# INT_RACK.net
KiCad netlist of a schematic drawn in EAGLE
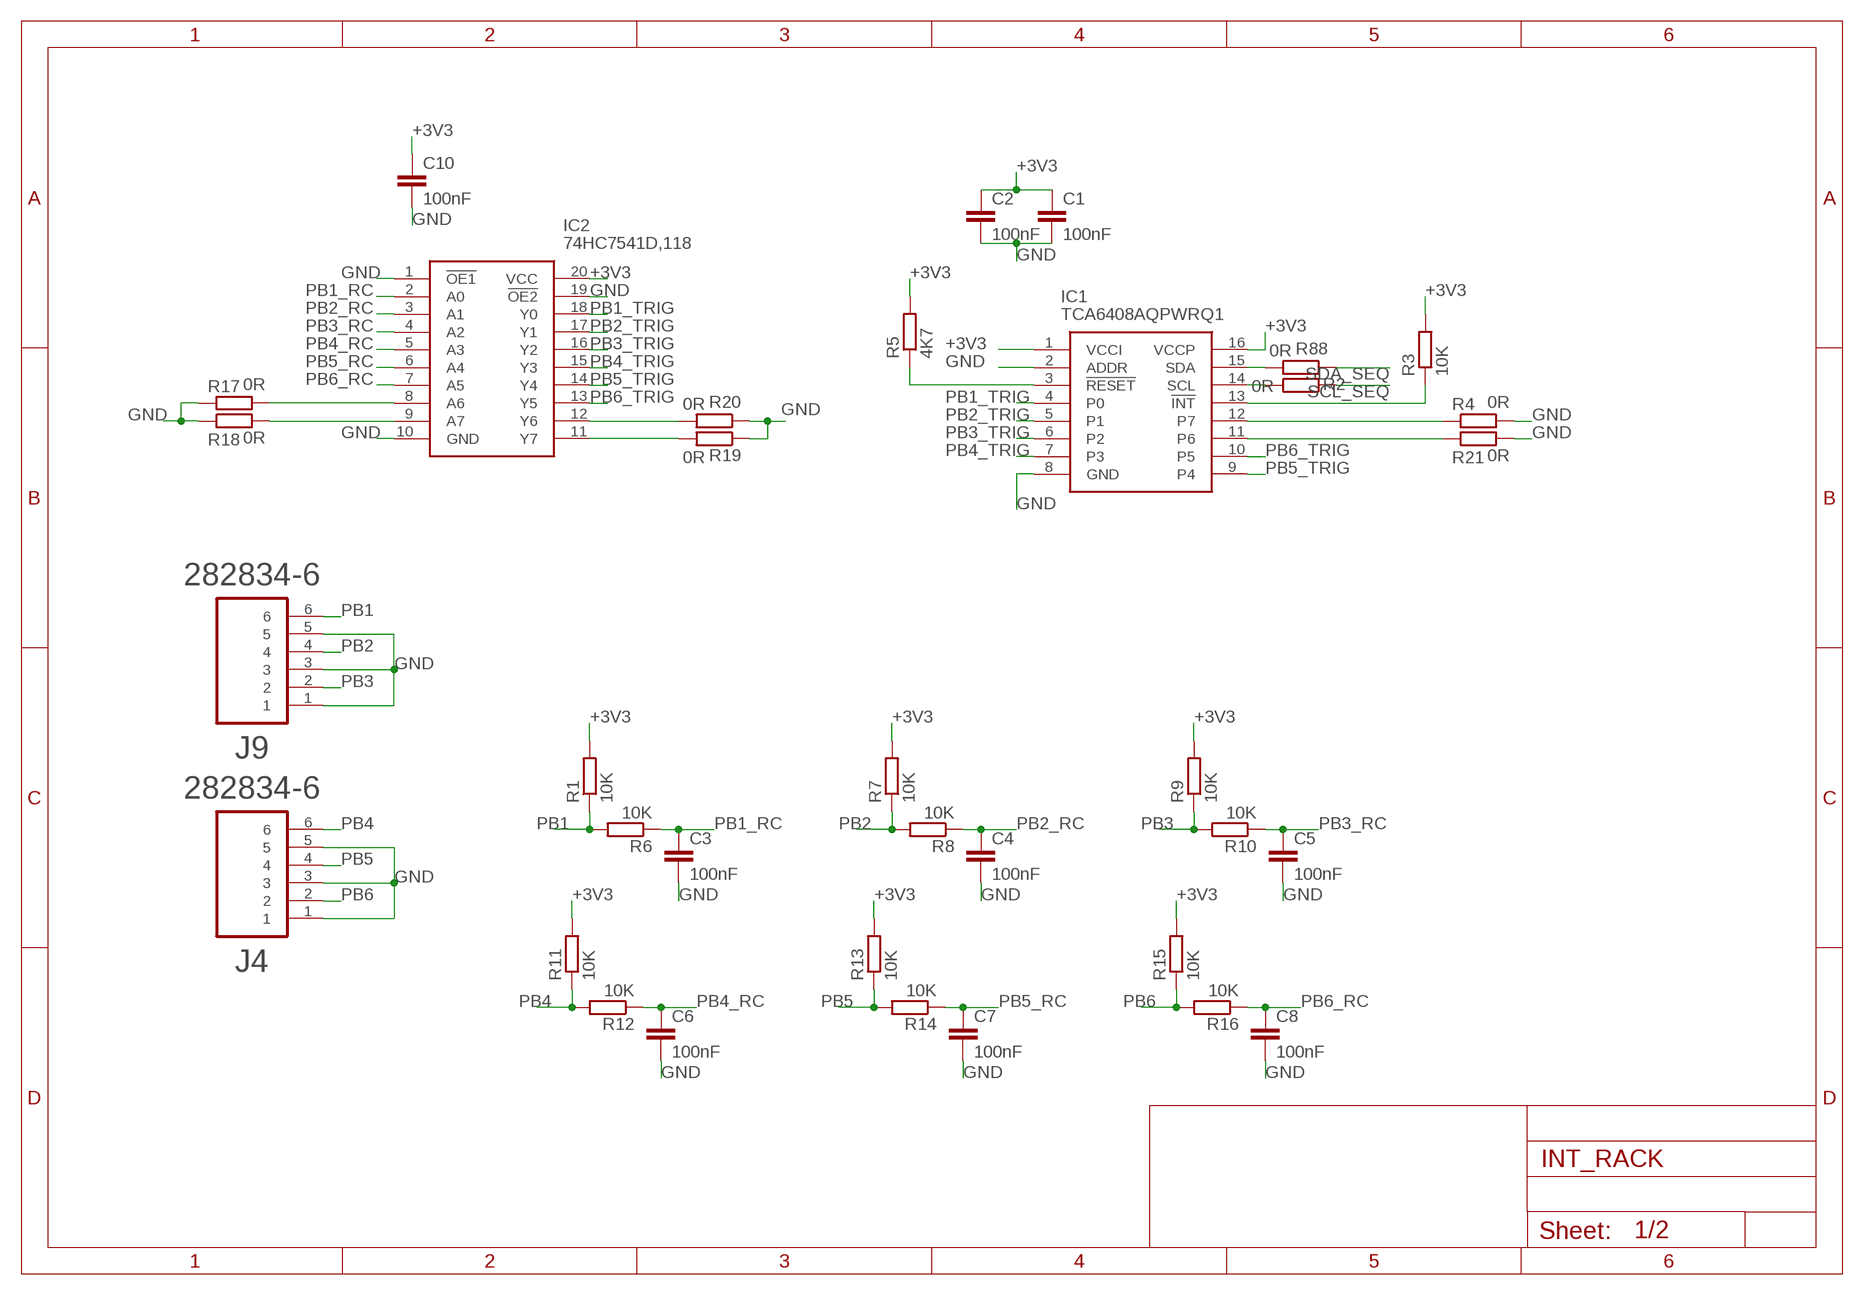
[diagram p0: schematic, sheet 1]
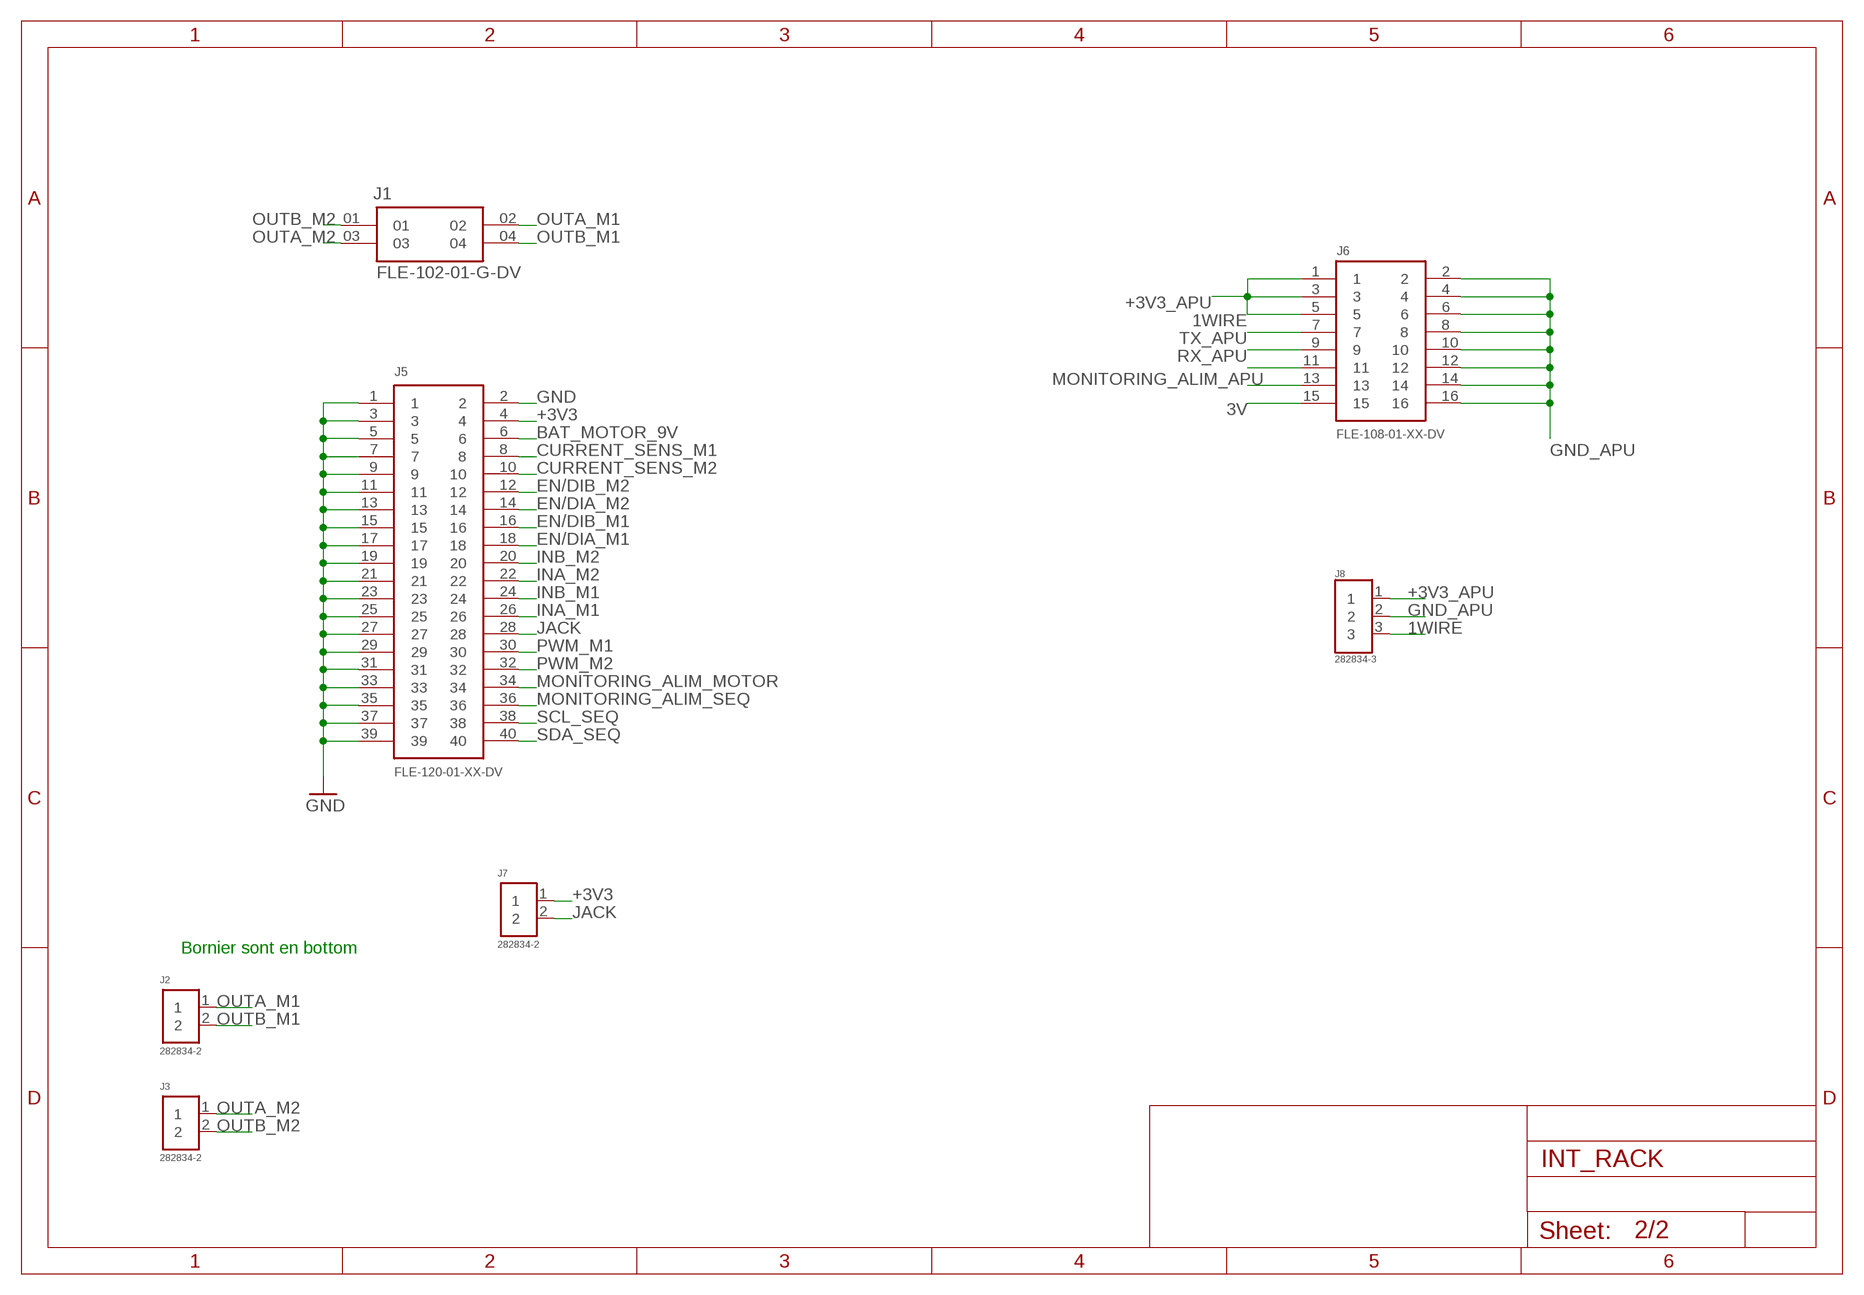
[diagram p1: schematic, sheet 2]

(export (version "E")
  (design (tool "Eeschema 10.0.6"))
  (components
    (comp (ref "C1")
      (value "100nF")
      (footprint "eagle-import:C0805")
      (libsource (lib "eagle-import") (part "C-EUC0805"))
    )
    (comp (ref "C2")
      (value "100nF")
      (footprint "eagle-import:C0805")
      (libsource (lib "eagle-import") (part "C-EUC0805"))
    )
    (comp (ref "C3")
      (value "100nF")
      (footprint "eagle-import:C0805")
      (libsource (lib "eagle-import") (part "C-EUC0805"))
    )
    (comp (ref "C4")
      (value "100nF")
      (footprint "eagle-import:C0805")
      (libsource (lib "eagle-import") (part "C-EUC0805"))
    )
    (comp (ref "C5")
      (value "100nF")
      (footprint "eagle-import:C0805")
      (libsource (lib "eagle-import") (part "C-EUC0805"))
    )
    (comp (ref "C6")
      (value "100nF")
      (footprint "eagle-import:C0805")
      (libsource (lib "eagle-import") (part "C-EUC0805"))
    )
    (comp (ref "C7")
      (value "100nF")
      (footprint "eagle-import:C0805")
      (libsource (lib "eagle-import") (part "C-EUC0805"))
    )
    (comp (ref "C8")
      (value "100nF")
      (footprint "eagle-import:C0805")
      (libsource (lib "eagle-import") (part "C-EUC0805"))
    )
    (comp (ref "C10")
      (value "100nF")
      (footprint "eagle-import:C0805")
      (libsource (lib "eagle-import") (part "C-EUC0805"))
    )
    (comp (ref "IC1")
      (value "TCA6408AQPWRQ1")
      (footprint "eagle-import:SOP65P640X120-16N")
      (fields (field (name "MOUSER_PART_NUMBER") "595-TCA6408AQPWRQ1"))
      (libsource (lib "eagle-import") (part "TCA6408AQPWRQ1"))
    )
    (comp (ref "IC2")
      (value "74HC7541D,118")
      (footprint "eagle-import:SOIC127P1032X265-20N")
      (fields (field (name "MOUSER_PART_NUMBER") "771-74HC7541D-T"))
      (libsource (lib "eagle-import") (part "74HC7541D,118"))
    )
    (comp (ref "J4")
      (value "282834-6")
      (footprint "eagle-import:TE_282834-6")
      (fields (field (name "MF") "TE Connectivity"))
      (libsource (lib "eagle-import") (part "282834-6"))
    )
    (comp (ref "J9")
      (value "282834-6")
      (footprint "eagle-import:TE_282834-6")
      (fields (field (name "MF") "TE Connectivity"))
      (libsource (lib "eagle-import") (part "282834-6"))
    )
    (comp (ref "R1")
      (value "10K")
      (footprint "eagle-import:R0603")
      (libsource (lib "eagle-import") (part "R-EU_R0603"))
    )
    (comp (ref "R2")
      (value "0R")
      (footprint "eagle-import:R0603")
      (libsource (lib "eagle-import") (part "R-EU_R0603"))
    )
    (comp (ref "R3")
      (value "10K")
      (footprint "eagle-import:R0603")
      (libsource (lib "eagle-import") (part "R-EU_R0603"))
    )
    (comp (ref "R4")
      (value "0R")
      (footprint "eagle-import:R0603")
      (libsource (lib "eagle-import") (part "R-EU_R0603"))
    )
    (comp (ref "R5")
      (value "4K7")
      (footprint "eagle-import:R0603")
      (libsource (lib "eagle-import") (part "R-EU_R0603"))
    )
    (comp (ref "R6")
      (value "10K")
      (footprint "eagle-import:R0603")
      (libsource (lib "eagle-import") (part "R-EU_R0603"))
    )
    (comp (ref "R7")
      (value "10K")
      (footprint "eagle-import:R0603")
      (libsource (lib "eagle-import") (part "R-EU_R0603"))
    )
    (comp (ref "R8")
      (value "10K")
      (footprint "eagle-import:R0603")
      (libsource (lib "eagle-import") (part "R-EU_R0603"))
    )
    (comp (ref "R9")
      (value "10K")
      (footprint "eagle-import:R0603")
      (libsource (lib "eagle-import") (part "R-EU_R0603"))
    )
    (comp (ref "R10")
      (value "10K")
      (footprint "eagle-import:R0603")
      (libsource (lib "eagle-import") (part "R-EU_R0603"))
    )
    (comp (ref "R11")
      (value "10K")
      (footprint "eagle-import:R0603")
      (libsource (lib "eagle-import") (part "R-EU_R0603"))
    )
    (comp (ref "R12")
      (value "10K")
      (footprint "eagle-import:R0603")
      (libsource (lib "eagle-import") (part "R-EU_R0603"))
    )
    (comp (ref "R13")
      (value "10K")
      (footprint "eagle-import:R0603")
      (libsource (lib "eagle-import") (part "R-EU_R0603"))
    )
    (comp (ref "R14")
      (value "10K")
      (footprint "eagle-import:R0603")
      (libsource (lib "eagle-import") (part "R-EU_R0603"))
    )
    (comp (ref "R15")
      (value "10K")
      (footprint "eagle-import:R0603")
      (libsource (lib "eagle-import") (part "R-EU_R0603"))
    )
    (comp (ref "R16")
      (value "10K")
      (footprint "eagle-import:R0603")
      (libsource (lib "eagle-import") (part "R-EU_R0603"))
    )
    (comp (ref "R17")
      (value "0R")
      (footprint "eagle-import:R0603")
      (libsource (lib "eagle-import") (part "R-EU_R0603"))
    )
    (comp (ref "R18")
      (value "0R")
      (footprint "eagle-import:R0603")
      (libsource (lib "eagle-import") (part "R-EU_R0603"))
    )
    (comp (ref "R19")
      (value "0R")
      (footprint "eagle-import:R0603")
      (libsource (lib "eagle-import") (part "R-EU_R0603"))
    )
    (comp (ref "R20")
      (value "0R")
      (footprint "eagle-import:R0603")
      (libsource (lib "eagle-import") (part "R-EU_R0603"))
    )
    (comp (ref "R21")
      (value "0R")
      (footprint "eagle-import:R0603")
      (libsource (lib "eagle-import") (part "R-EU_R0603"))
    )
    (comp (ref "R88")
      (value "0R")
      (footprint "eagle-import:R0603")
      (libsource (lib "eagle-import") (part "R-EU_R0603"))
    )
    (comp (ref "J1")
      (value "FLE-102-01-G-DV")
      (footprint "eagle-import:SAMTEC_FLE-102-01-G-DV")
      (fields (field (name "MF") "Samtec"))
      (libsource (lib "eagle-import") (part "FLE-102-01-G-DV"))
    )
    (comp (ref "J2")
      (value "282834-2")
      (footprint "eagle-import:CONN_282834-2")
      (fields (field (name "MF") "TE Connectivity"))
      (libsource (lib "eagle-import") (part "282834-2"))
    )
    (comp (ref "J3")
      (value "282834-2")
      (footprint "eagle-import:CONN_282834-2")
      (fields (field (name "MF") "TE Connectivity"))
      (libsource (lib "eagle-import") (part "282834-2"))
    )
    (comp (ref "J5")
      (value "FLE-120-01-XX-DV")
      (footprint "eagle-import:FLE-120-01-XX-DV")
      (fields (field (name "MF") "Samtec") (field (name "MP") "FLE-120-01-G-DV"))
      (libsource (lib "eagle-import") (part "FLE-120-01-XX-DV"))
    )
    (comp (ref "J6")
      (value "FLE-108-01-XX-DV")
      (footprint "eagle-import:FLE-108-01-XX-DV")
      (fields (field (name "MF") "Samtec") (field (name "MP") "FLE-108-01-G-DV"))
      (libsource (lib "eagle-import") (part "FLE-108-01-XX-DV"))
    )
    (comp (ref "J7")
      (value "282834-2")
      (footprint "eagle-import:CONN_282834-2")
      (fields (field (name "MF") "TE Connectivity"))
      (libsource (lib "eagle-import") (part "282834-2"))
    )
    (comp (ref "J8")
      (value "282834-3")
      (footprint "eagle-import:TE_282834-3")
      (fields (field (name "MF") "TE Connectivity"))
      (libsource (lib "eagle-import") (part "282834-3"))
    )
  )
  (nets
    (net (code "1") (name "+3V3") (class "Default")
      (node (ref "C1") (pin "1") (pinfunction "1_1") (pintype "passive"))
      (node (ref "C10") (pin "1") (pinfunction "1_1") (pintype "passive"))
      (node (ref "C2") (pin "1") (pinfunction "1_1") (pintype "passive"))
      (node (ref "IC1") (pin "1") (pinfunction "VCCI_1") (pintype "bidirectional"))
      (node (ref "IC1") (pin "16") (pinfunction "VCCP_16") (pintype "bidirectional"))
      (node (ref "IC2") (pin "20") (pinfunction "VCC_20") (pintype "bidirectional"))
      (node (ref "J5") (pin "4") (pinfunction "4_4") (pintype "bidirectional"))
      (node (ref "J7") (pin "1") (pinfunction "1_1") (pintype "passive"))
      (node (ref "R1") (pin "2") (pinfunction "2_2") (pintype "passive"))
      (node (ref "R11") (pin "2") (pinfunction "2_2") (pintype "passive"))
      (node (ref "R13") (pin "2") (pinfunction "2_2") (pintype "passive"))
      (node (ref "R15") (pin "2") (pinfunction "2_2") (pintype "passive"))
      (node (ref "R3") (pin "2") (pinfunction "2_2") (pintype "passive"))
      (node (ref "R5") (pin "2") (pinfunction "2_2") (pintype "passive"))
      (node (ref "R7") (pin "2") (pinfunction "2_2") (pintype "passive"))
      (node (ref "R9") (pin "2") (pinfunction "2_2") (pintype "passive"))
    )
    (net (code "2") (name "+3V3_APU") (class "Default")
      (node (ref "J6") (pin "1") (pinfunction "1_1") (pintype "bidirectional"))
      (node (ref "J6") (pin "3") (pinfunction "3_3") (pintype "bidirectional"))
      (node (ref "J6") (pin "5") (pinfunction "5_5") (pintype "bidirectional"))
      (node (ref "J8") (pin "1") (pinfunction "1_1") (pintype "passive"))
    )
    (net (code "3") (name "1WIRE") (class "Default")
      (node (ref "J6") (pin "7") (pinfunction "7_7") (pintype "bidirectional"))
      (node (ref "J8") (pin "3") (pinfunction "3_3") (pintype "passive"))
    )
    (net (code "4") (name "3V") (class "Default")
      (node (ref "J6") (pin "15") (pinfunction "15_15") (pintype "bidirectional"))
    )
    (net (code "5") (name "BAT_MOTOR_9V") (class "Default")
      (node (ref "J5") (pin "6") (pinfunction "6_6") (pintype "bidirectional"))
    )
    (net (code "6") (name "CURRENT_SENS_M1") (class "Default")
      (node (ref "J5") (pin "8") (pinfunction "8_8") (pintype "bidirectional"))
    )
    (net (code "7") (name "CURRENT_SENS_M2") (class "Default")
      (node (ref "J5") (pin "10") (pinfunction "10_10") (pintype "bidirectional"))
    )
    (net (code "8") (name "EN{slash}DIA_M1") (class "Default")
      (node (ref "J5") (pin "18") (pinfunction "18_18") (pintype "bidirectional"))
    )
    (net (code "9") (name "EN{slash}DIA_M2") (class "Default")
      (node (ref "J5") (pin "14") (pinfunction "14_14") (pintype "bidirectional"))
    )
    (net (code "10") (name "EN{slash}DIB_M1") (class "Default")
      (node (ref "J5") (pin "16") (pinfunction "16_16") (pintype "bidirectional"))
    )
    (net (code "11") (name "EN{slash}DIB_M2") (class "Default")
      (node (ref "J5") (pin "12") (pinfunction "12_12") (pintype "bidirectional"))
    )
    (net (code "12") (name "GND") (class "Default")
      (node (ref "C1") (pin "2") (pinfunction "2_2") (pintype "passive"))
      (node (ref "C10") (pin "2") (pinfunction "2_2") (pintype "passive"))
      (node (ref "C2") (pin "2") (pinfunction "2_2") (pintype "passive"))
      (node (ref "C3") (pin "2") (pinfunction "2_2") (pintype "passive"))
      (node (ref "C4") (pin "2") (pinfunction "2_2") (pintype "passive"))
      (node (ref "C5") (pin "2") (pinfunction "2_2") (pintype "passive"))
      (node (ref "C6") (pin "2") (pinfunction "2_2") (pintype "passive"))
      (node (ref "C7") (pin "2") (pinfunction "2_2") (pintype "passive"))
      (node (ref "C8") (pin "2") (pinfunction "2_2") (pintype "passive"))
      (node (ref "IC1") (pin "2") (pinfunction "ADDR_2") (pintype "bidirectional"))
      (node (ref "IC1") (pin "8") (pinfunction "GND_8") (pintype "bidirectional"))
      (node (ref "IC2") (pin "1") (pinfunction "~{OE1}_1") (pintype "bidirectional"))
      (node (ref "IC2") (pin "10") (pinfunction "GND_10") (pintype "bidirectional"))
      (node (ref "IC2") (pin "19") (pinfunction "~{OE2}_19") (pintype "bidirectional"))
      (node (ref "J4") (pin "1") (pinfunction "1_1") (pintype "passive"))
      (node (ref "J4") (pin "3") (pinfunction "3_3") (pintype "passive"))
      (node (ref "J4") (pin "5") (pinfunction "5_5") (pintype "passive"))
      (node (ref "J5") (pin "1") (pinfunction "1_1") (pintype "bidirectional"))
      (node (ref "J5") (pin "11") (pinfunction "11_11") (pintype "bidirectional"))
      (node (ref "J5") (pin "13") (pinfunction "13_13") (pintype "bidirectional"))
      (node (ref "J5") (pin "15") (pinfunction "15_15") (pintype "bidirectional"))
      (node (ref "J5") (pin "17") (pinfunction "17_17") (pintype "bidirectional"))
      (node (ref "J5") (pin "19") (pinfunction "19_19") (pintype "bidirectional"))
      (node (ref "J5") (pin "2") (pinfunction "2_2") (pintype "bidirectional"))
      (node (ref "J5") (pin "21") (pinfunction "21_21") (pintype "bidirectional"))
      (node (ref "J5") (pin "23") (pinfunction "23_23") (pintype "bidirectional"))
      (node (ref "J5") (pin "25") (pinfunction "25_25") (pintype "bidirectional"))
      (node (ref "J5") (pin "27") (pinfunction "27_27") (pintype "bidirectional"))
      (node (ref "J5") (pin "29") (pinfunction "29_29") (pintype "bidirectional"))
      (node (ref "J5") (pin "3") (pinfunction "3_3") (pintype "bidirectional"))
      (node (ref "J5") (pin "31") (pinfunction "31_31") (pintype "bidirectional"))
      (node (ref "J5") (pin "33") (pinfunction "33_33") (pintype "bidirectional"))
      (node (ref "J5") (pin "35") (pinfunction "35_35") (pintype "bidirectional"))
      (node (ref "J5") (pin "37") (pinfunction "37_37") (pintype "bidirectional"))
      (node (ref "J5") (pin "39") (pinfunction "39_39") (pintype "bidirectional"))
      (node (ref "J5") (pin "5") (pinfunction "5_5") (pintype "bidirectional"))
      (node (ref "J5") (pin "7") (pinfunction "7_7") (pintype "bidirectional"))
      (node (ref "J5") (pin "9") (pinfunction "9_9") (pintype "bidirectional"))
      (node (ref "J9") (pin "1") (pinfunction "1_1") (pintype "passive"))
      (node (ref "J9") (pin "3") (pinfunction "3_3") (pintype "passive"))
      (node (ref "J9") (pin "5") (pinfunction "5_5") (pintype "passive"))
      (node (ref "R17") (pin "1") (pinfunction "1_1") (pintype "passive"))
      (node (ref "R18") (pin "1") (pinfunction "1_1") (pintype "passive"))
      (node (ref "R19") (pin "1") (pinfunction "1_1") (pintype "passive"))
      (node (ref "R20") (pin "1") (pinfunction "1_1") (pintype "passive"))
      (node (ref "R21") (pin "2") (pinfunction "2_2") (pintype "passive"))
      (node (ref "R4") (pin "2") (pinfunction "2_2") (pintype "passive"))
    )
    (net (code "13") (name "GND_APU") (class "Default")
      (node (ref "J6") (pin "10") (pinfunction "10_10") (pintype "bidirectional"))
      (node (ref "J6") (pin "12") (pinfunction "12_12") (pintype "bidirectional"))
      (node (ref "J6") (pin "14") (pinfunction "14_14") (pintype "bidirectional"))
      (node (ref "J6") (pin "16") (pinfunction "16_16") (pintype "bidirectional"))
      (node (ref "J6") (pin "2") (pinfunction "2_2") (pintype "bidirectional"))
      (node (ref "J6") (pin "4") (pinfunction "4_4") (pintype "bidirectional"))
      (node (ref "J6") (pin "6") (pinfunction "6_6") (pintype "bidirectional"))
      (node (ref "J6") (pin "8") (pinfunction "8_8") (pintype "bidirectional"))
      (node (ref "J8") (pin "2") (pinfunction "2_2") (pintype "passive"))
    )
    (net (code "14") (name "INA_M1") (class "Default")
      (node (ref "J5") (pin "26") (pinfunction "26_26") (pintype "bidirectional"))
    )
    (net (code "15") (name "INA_M2") (class "Default")
      (node (ref "J5") (pin "22") (pinfunction "22_22") (pintype "bidirectional"))
    )
    (net (code "16") (name "INB_M1") (class "Default")
      (node (ref "J5") (pin "24") (pinfunction "24_24") (pintype "bidirectional"))
    )
    (net (code "17") (name "INB_M2") (class "Default")
      (node (ref "J5") (pin "20") (pinfunction "20_20") (pintype "bidirectional"))
    )
    (net (code "18") (name "JACK") (class "Default")
      (node (ref "J5") (pin "28") (pinfunction "28_28") (pintype "bidirectional"))
      (node (ref "J7") (pin "2") (pinfunction "2_2") (pintype "passive"))
    )
    (net (code "19") (name "MONITORING_ALIM_APU") (class "Default")
      (node (ref "J6") (pin "13") (pinfunction "13_13") (pintype "bidirectional"))
    )
    (net (code "20") (name "MONITORING_ALIM_MOTOR") (class "Default")
      (node (ref "J5") (pin "34") (pinfunction "34_34") (pintype "bidirectional"))
    )
    (net (code "21") (name "MONITORING_ALIM_SEQ") (class "Default")
      (node (ref "J5") (pin "36") (pinfunction "36_36") (pintype "bidirectional"))
    )
    (net (code "22") (name "Net-(IC1-P6)") (class "Default")
      (node (ref "IC1") (pin "11") (pinfunction "P6_11") (pintype "bidirectional"))
      (node (ref "R21") (pin "1") (pinfunction "1_1") (pintype "passive"))
    )
    (net (code "23") (name "Net-(IC1-P7)") (class "Default")
      (node (ref "IC1") (pin "12") (pinfunction "P7_12") (pintype "bidirectional"))
      (node (ref "R4") (pin "1") (pinfunction "1_1") (pintype "passive"))
    )
    (net (code "24") (name "Net-(IC1-SCL)") (class "Default")
      (node (ref "IC1") (pin "14") (pinfunction "SCL_14") (pintype "bidirectional"))
      (node (ref "R2") (pin "2") (pinfunction "2_2") (pintype "passive"))
    )
    (net (code "25") (name "Net-(IC1-SDA)") (class "Default")
      (node (ref "IC1") (pin "15") (pinfunction "SDA_15") (pintype "bidirectional"))
      (node (ref "R88") (pin "2") (pinfunction "2_2") (pintype "passive"))
    )
    (net (code "26") (name "Net-(IC1-~{INT})") (class "Default")
      (node (ref "IC1") (pin "13") (pinfunction "~{INT}_13") (pintype "bidirectional"))
      (node (ref "R3") (pin "1") (pinfunction "1_1") (pintype "passive"))
    )
    (net (code "27") (name "Net-(IC1-~{RESET})") (class "Default")
      (node (ref "IC1") (pin "3") (pinfunction "~{RESET}_3") (pintype "bidirectional"))
      (node (ref "R5") (pin "1") (pinfunction "1_1") (pintype "passive"))
    )
    (net (code "28") (name "Net-(IC2-A6)") (class "Default")
      (node (ref "IC2") (pin "8") (pinfunction "A6_8") (pintype "bidirectional"))
      (node (ref "R17") (pin "2") (pinfunction "2_2") (pintype "passive"))
    )
    (net (code "29") (name "Net-(IC2-A7)") (class "Default")
      (node (ref "IC2") (pin "9") (pinfunction "A7_9") (pintype "bidirectional"))
      (node (ref "R18") (pin "2") (pinfunction "2_2") (pintype "passive"))
    )
    (net (code "30") (name "Net-(IC2-Y6)") (class "Default")
      (node (ref "IC2") (pin "12") (pinfunction "Y6_12") (pintype "bidirectional"))
      (node (ref "R20") (pin "2") (pinfunction "2_2") (pintype "passive"))
    )
    (net (code "31") (name "Net-(IC2-Y7)") (class "Default")
      (node (ref "IC2") (pin "11") (pinfunction "Y7_11") (pintype "bidirectional"))
      (node (ref "R19") (pin "2") (pinfunction "2_2") (pintype "passive"))
    )
    (net (code "32") (name "OUTA_M1") (class "Default")
      (node (ref "J1") (pin "02") (pinfunction "02_02") (pintype "passive"))
      (node (ref "J2") (pin "1") (pinfunction "1_1") (pintype "passive"))
    )
    (net (code "33") (name "OUTA_M2") (class "Default")
      (node (ref "J1") (pin "03") (pinfunction "03_03") (pintype "passive"))
      (node (ref "J3") (pin "1") (pinfunction "1_1") (pintype "passive"))
    )
    (net (code "34") (name "OUTB_M1") (class "Default")
      (node (ref "J1") (pin "04") (pinfunction "04_04") (pintype "passive"))
      (node (ref "J2") (pin "2") (pinfunction "2_2") (pintype "passive"))
    )
    (net (code "35") (name "OUTB_M2") (class "Default")
      (node (ref "J1") (pin "01") (pinfunction "01_01") (pintype "passive"))
      (node (ref "J3") (pin "2") (pinfunction "2_2") (pintype "passive"))
    )
    (net (code "36") (name "PB1") (class "Default")
      (node (ref "J9") (pin "6") (pinfunction "6_6") (pintype "passive"))
      (node (ref "R1") (pin "1") (pinfunction "1_1") (pintype "passive"))
      (node (ref "R6") (pin "2") (pinfunction "2_2") (pintype "passive"))
    )
    (net (code "37") (name "PB1_RC") (class "Default")
      (node (ref "C3") (pin "1") (pinfunction "1_1") (pintype "passive"))
      (node (ref "IC2") (pin "2") (pinfunction "A0_2") (pintype "bidirectional"))
      (node (ref "R6") (pin "1") (pinfunction "1_1") (pintype "passive"))
    )
    (net (code "38") (name "PB1_TRIG") (class "Default")
      (node (ref "IC1") (pin "4") (pinfunction "P0_4") (pintype "bidirectional"))
      (node (ref "IC2") (pin "18") (pinfunction "Y0_18") (pintype "bidirectional"))
    )
    (net (code "39") (name "PB2") (class "Default")
      (node (ref "J9") (pin "4") (pinfunction "4_4") (pintype "passive"))
      (node (ref "R7") (pin "1") (pinfunction "1_1") (pintype "passive"))
      (node (ref "R8") (pin "2") (pinfunction "2_2") (pintype "passive"))
    )
    (net (code "40") (name "PB2_RC") (class "Default")
      (node (ref "C4") (pin "1") (pinfunction "1_1") (pintype "passive"))
      (node (ref "IC2") (pin "3") (pinfunction "A1_3") (pintype "bidirectional"))
      (node (ref "R8") (pin "1") (pinfunction "1_1") (pintype "passive"))
    )
    (net (code "41") (name "PB2_TRIG") (class "Default")
      (node (ref "IC1") (pin "5") (pinfunction "P1_5") (pintype "bidirectional"))
      (node (ref "IC2") (pin "17") (pinfunction "Y1_17") (pintype "bidirectional"))
    )
    (net (code "42") (name "PB3") (class "Default")
      (node (ref "J9") (pin "2") (pinfunction "2_2") (pintype "passive"))
      (node (ref "R10") (pin "2") (pinfunction "2_2") (pintype "passive"))
      (node (ref "R9") (pin "1") (pinfunction "1_1") (pintype "passive"))
    )
    (net (code "43") (name "PB3_RC") (class "Default")
      (node (ref "C5") (pin "1") (pinfunction "1_1") (pintype "passive"))
      (node (ref "IC2") (pin "4") (pinfunction "A2_4") (pintype "bidirectional"))
      (node (ref "R10") (pin "1") (pinfunction "1_1") (pintype "passive"))
    )
    (net (code "44") (name "PB3_TRIG") (class "Default")
      (node (ref "IC1") (pin "6") (pinfunction "P2_6") (pintype "bidirectional"))
      (node (ref "IC2") (pin "16") (pinfunction "Y2_16") (pintype "bidirectional"))
    )
    (net (code "45") (name "PB4") (class "Default")
      (node (ref "J4") (pin "6") (pinfunction "6_6") (pintype "passive"))
      (node (ref "R11") (pin "1") (pinfunction "1_1") (pintype "passive"))
      (node (ref "R12") (pin "2") (pinfunction "2_2") (pintype "passive"))
    )
    (net (code "46") (name "PB4_RC") (class "Default")
      (node (ref "C6") (pin "1") (pinfunction "1_1") (pintype "passive"))
      (node (ref "IC2") (pin "5") (pinfunction "A3_5") (pintype "bidirectional"))
      (node (ref "R12") (pin "1") (pinfunction "1_1") (pintype "passive"))
    )
    (net (code "47") (name "PB4_TRIG") (class "Default")
      (node (ref "IC1") (pin "7") (pinfunction "P3_7") (pintype "bidirectional"))
      (node (ref "IC2") (pin "15") (pinfunction "Y3_15") (pintype "bidirectional"))
    )
    (net (code "48") (name "PB5") (class "Default")
      (node (ref "J4") (pin "4") (pinfunction "4_4") (pintype "passive"))
      (node (ref "R13") (pin "1") (pinfunction "1_1") (pintype "passive"))
      (node (ref "R14") (pin "2") (pinfunction "2_2") (pintype "passive"))
    )
    (net (code "49") (name "PB5_RC") (class "Default")
      (node (ref "C7") (pin "1") (pinfunction "1_1") (pintype "passive"))
      (node (ref "IC2") (pin "6") (pinfunction "A4_6") (pintype "bidirectional"))
      (node (ref "R14") (pin "1") (pinfunction "1_1") (pintype "passive"))
    )
    (net (code "50") (name "PB5_TRIG") (class "Default")
      (node (ref "IC1") (pin "9") (pinfunction "P4_9") (pintype "bidirectional"))
      (node (ref "IC2") (pin "14") (pinfunction "Y4_14") (pintype "bidirectional"))
    )
    (net (code "51") (name "PB6") (class "Default")
      (node (ref "J4") (pin "2") (pinfunction "2_2") (pintype "passive"))
      (node (ref "R15") (pin "1") (pinfunction "1_1") (pintype "passive"))
      (node (ref "R16") (pin "2") (pinfunction "2_2") (pintype "passive"))
    )
    (net (code "52") (name "PB6_RC") (class "Default")
      (node (ref "C8") (pin "1") (pinfunction "1_1") (pintype "passive"))
      (node (ref "IC2") (pin "7") (pinfunction "A5_7") (pintype "bidirectional"))
      (node (ref "R16") (pin "1") (pinfunction "1_1") (pintype "passive"))
    )
    (net (code "53") (name "PB6_TRIG") (class "Default")
      (node (ref "IC1") (pin "10") (pinfunction "P5_10") (pintype "bidirectional"))
      (node (ref "IC2") (pin "13") (pinfunction "Y5_13") (pintype "bidirectional"))
    )
    (net (code "54") (name "PWM_M1") (class "Default")
      (node (ref "J5") (pin "30") (pinfunction "30_30") (pintype "bidirectional"))
    )
    (net (code "55") (name "PWM_M2") (class "Default")
      (node (ref "J5") (pin "32") (pinfunction "32_32") (pintype "bidirectional"))
    )
    (net (code "56") (name "RX_APU") (class "Default")
      (node (ref "J6") (pin "11") (pinfunction "11_11") (pintype "bidirectional"))
    )
    (net (code "57") (name "SCL_SEQ") (class "Default")
      (node (ref "J5") (pin "38") (pinfunction "38_38") (pintype "bidirectional"))
      (node (ref "R2") (pin "1") (pinfunction "1_1") (pintype "passive"))
    )
    (net (code "58") (name "SDA_SEQ") (class "Default")
      (node (ref "J5") (pin "40") (pinfunction "40_40") (pintype "bidirectional"))
      (node (ref "R88") (pin "1") (pinfunction "1_1") (pintype "passive"))
    )
    (net (code "59") (name "TX_APU") (class "Default")
      (node (ref "J6") (pin "9") (pinfunction "9_9") (pintype "bidirectional"))
    )
  )
)
